# MCU.net
KiCad netlist of a schematic drawn in Altium Designer
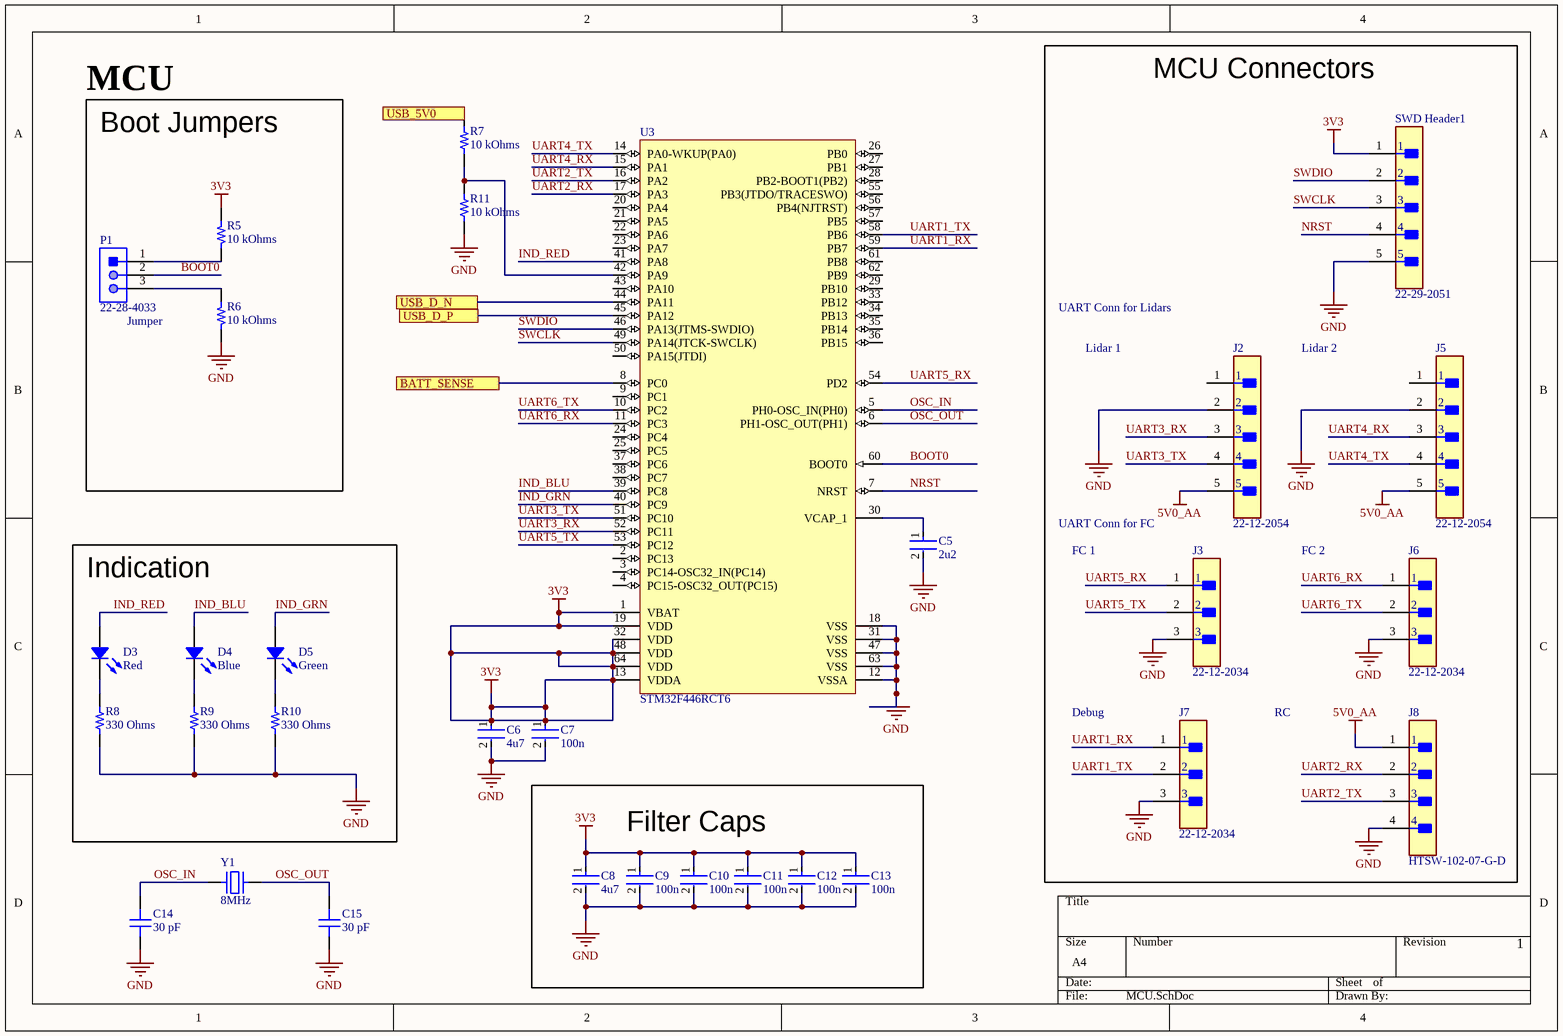
[diagram p0: MCU.SchDoc]

(export (version "E")
  (design (tool "Eeschema 10.0.6"))
  (components
    (comp (ref "C5")
      (value "2u2")
      (footprint "FP-CL10-IPC_C")
      (description "Cap Ceramic 4.7uF 10V X5R ±10% Pad SMD 0603 +85°C T/R")
      (fields (field (name "TOLERANCE") "10%"))
      (libsource (lib "Altium Content Vault") (part "b4654b650e69147ec39a6b967a45e02"))
    )
    (comp (ref "C6")
      (value "4u7")
      (footprint "FP-CL10-IPC_C")
      (description "Cap Ceramic 4.7uF 10V X5R ±10% Pad SMD 0603 +85°C T/R")
      (fields (field (name "TOLERANCE") "10%"))
      (libsource (lib "Altium Content Vault") (part "b4654b650e69147ec39a6b967a45e02"))
    )
    (comp (ref "C7")
      (value "100n")
      (footprint "FP-CL779-IPC_C")
      (description "Cap Ceramic 100nF 50V X7R ±10% SMD 0402 +125°C Paper T/R")
      (libsource (lib "Altium Content Vault") (part "b4654b650e69147ec39a6b967a45e02"))
    )
    (comp (ref "C8")
      (value "4u7")
      (footprint "FP-CL10-IPC_C")
      (description "Cap Ceramic 4.7uF 10V X5R ±10% Pad SMD 0603 +85°C T/R")
      (fields (field (name "TOLERANCE") "10%"))
      (libsource (lib "Altium Content Vault") (part "b4654b650e69147ec39a6b967a45e02"))
    )
    (comp (ref "C9")
      (value "100n")
      (footprint "FP-CL779-IPC_C")
      (description "Cap Ceramic 100nF 50V X7R ±10% SMD 0402 +125°C Paper T/R")
      (libsource (lib "Altium Content Vault") (part "b4654b650e69147ec39a6b967a45e02"))
    )
    (comp (ref "C10")
      (value "100n")
      (footprint "FP-CL779-IPC_C")
      (description "Cap Ceramic 100nF 50V X7R ±10% SMD 0402 +125°C Paper T/R")
      (libsource (lib "Altium Content Vault") (part "b4654b650e69147ec39a6b967a45e02"))
    )
    (comp (ref "C11")
      (value "100n")
      (footprint "FP-CL779-IPC_C")
      (description "Cap Ceramic 100nF 50V X7R ±10% SMD 0402 +125°C Paper T/R")
      (libsource (lib "Altium Content Vault") (part "b4654b650e69147ec39a6b967a45e02"))
    )
    (comp (ref "C12")
      (value "100n")
      (footprint "FP-CL779-IPC_C")
      (description "Cap Ceramic 100nF 50V X7R ±10% SMD 0402 +125°C Paper T/R")
      (libsource (lib "Altium Content Vault") (part "b4654b650e69147ec39a6b967a45e02"))
    )
    (comp (ref "C13")
      (value "100n")
      (footprint "FP-CL779-IPC_C")
      (description "Cap Ceramic 100nF 50V X7R ±10% SMD 0402 +125°C Paper T/R")
      (libsource (lib "Altium Content Vault") (part "b4654b650e69147ec39a6b967a45e02"))
    )
    (comp (ref "C14")
      (value "30 pF")
      (footprint "CAP 0603_1608")
      (description "CAP CER 30PF 50V C0G/NP0 0603")
      (fields
        (field (name "PART NUMBER") "0603N300J500CT")
        (field (name "MANUFACTURER") "Walsin Technology Corporation")
      )
      (libsource (lib "Celestial Altium Library - altium_library") (part "Capacitor"))
    )
    (comp (ref "C15")
      (value "30 pF")
      (footprint "CAP 0603_1608")
      (description "CAP CER 30PF 50V C0G/NP0 0603")
      (fields
        (field (name "PART NUMBER") "0603N300J500CT")
        (field (name "MANUFACTURER") "Walsin Technology Corporation")
      )
      (libsource (lib "Celestial Altium Library - altium_library") (part "Capacitor"))
    )
    (comp (ref "D3")
      (value "Red")
      (footprint "LED 0603_1608 RED")
      (description "LED RED CLEAR 2SMD")
      (fields
        (field (name "PART NUMBER") "19-213SDRC/S259/TR8")
        (field (name "MANUFACTURER") "Everlight Electronics Co Ltd")
      )
      (libsource (lib "Celestial Altium Library - altium_library") (part "LED"))
    )
    (comp (ref "D4")
      (value "Blue")
      (footprint "LED 0603_1608 BLUE")
      (description "LED BLUE CLEAR 2SMD")
      (fields
        (field (name "PART NUMBER") "19-213SUBC/S400-A5/S208-2/TR8")
        (field (name "MANUFACTURER") "Everlight Electronics Co Ltd")
      )
      (libsource (lib "Celestial Altium Library - altium_library") (part "LED"))
    )
    (comp (ref "D5")
      (value "Green")
      (footprint "LED 0603_1608 GREEN")
      (description "LED GREEN DIFFUSED 0603 SMD")
      (fields (field (name "PART NUMBER") "150060GS55040") (field (name "MANUFACTURER") "Würth Elektronik"))
      (libsource (lib "Celestial Altium Library - altium_library") (part "LED"))
    )
    (comp (ref "J2")
      (value "22-12-2054")
      (footprint "FP-22-12-2054-MFG")
      (libsource (lib "Altium Content Vault") (part "bf93c07fd2649a848d0ec8585582aab"))
    )
    (comp (ref "J3")
      (value "22-12-2034")
      (footprint "FP-22-12-2034-MFG")
      (description "CONN HEADER R/A 3POS 2.54MM")
      (libsource (lib "Altium Content Vault") (part "0d3f023dd272f625e17a2be33dea85f"))
    )
    (comp (ref "J5")
      (value "22-12-2054")
      (footprint "FP-22-12-2054-MFG")
      (libsource (lib "Altium Content Vault") (part "bf93c07fd2649a848d0ec8585582aab"))
    )
    (comp (ref "J6")
      (value "22-12-2034")
      (footprint "FP-22-12-2034-MFG")
      (description "CONN HEADER R/A 3POS 2.54MM")
      (libsource (lib "Altium Content Vault") (part "0d3f023dd272f625e17a2be33dea85f"))
    )
    (comp (ref "J7")
      (value "22-12-2034")
      (footprint "FP-22-12-2034-MFG")
      (description "CONN HEADER R/A 3POS 2.54MM")
      (libsource (lib "Altium Content Vault") (part "0d3f023dd272f625e17a2be33dea85f"))
    )
    (comp (ref "J8")
      (value "HTSW-102-07-G-D")
      (footprint "FP-HTSW-102-07-G-D-MFG")
      (description "Connector Header Through Hole 4 position 0.100\" (2.54mm)")
      (fields (field (name "MANUFACTURER") "Samtec"))
      (libsource (lib "Altium Content Vault") (part "299a8cea1bdcbc3624fe62c390fa72c"))
    )
    (comp (ref "P1")
      (value "22-28-4033")
      (footprint "MOLX-22-28-4033_V")
      (description "Male Header, Pitch 2.54 mm, 1 x 3 Position, Height 8.38 mm, Tail Length 3.18 mm, RoHS, Bulk")
      (fields (field (name "MANUFACTURER") "Molex"))
      (libsource (lib "Altium Content Vault") (part "CN-1P-M-R3"))
    )
    (comp (ref "R5")
      (value "10 kOhms")
      (footprint "RES 0603_1608")
      (description "P2TC0603 2PPM/C 10K 0,01% N TA")
      (fields
        (field (name "PART NUMBER") "P2TC0603D1002LNTA")
        (field (name "MANUFACTURER") "Vishay Sfernice")
      )
      (libsource (lib "Celestial Altium Library - altium_library") (part "Resistor"))
    )
    (comp (ref "R6")
      (value "10 kOhms")
      (footprint "RES 0603_1608")
      (description "P2TC0603 2PPM/C 10K 0,01% N TA")
      (fields
        (field (name "PART NUMBER") "P2TC0603D1002LNTA")
        (field (name "MANUFACTURER") "Vishay Sfernice")
      )
      (libsource (lib "Celestial Altium Library - altium_library") (part "Resistor"))
    )
    (comp (ref "R7")
      (value "10 kOhms")
      (footprint "RES 0603_1608")
      (description "1/16 WATTS PRECISION CHIP 10 KIL")
      (fields (field (name "PART NUMBER") "APC0603B10K0N") (field (name "MANUFACTURER") "Ohmite"))
      (libsource (lib "Celestial Altium Library - altium_library") (part "Resistor"))
    )
    (comp (ref "R8")
      (value "330 Ohms")
      (footprint "RES 0603_1608")
      (description "RCC0603 100 330R 1% ET1 E3")
      (fields (field (name "PART NUMBER") "RCC0603330RFKEA") (field (name "MANUFACTURER") "Vishay Dale"))
      (libsource (lib "Celestial Altium Library - altium_library") (part "Resistor"))
    )
    (comp (ref "R9")
      (value "330 Ohms")
      (footprint "RES 0603_1608")
      (description "RCC0603 100 330R 1% ET1 E3")
      (fields (field (name "PART NUMBER") "RCC0603330RFKEA") (field (name "MANUFACTURER") "Vishay Dale"))
      (libsource (lib "Celestial Altium Library - altium_library") (part "Resistor"))
    )
    (comp (ref "R10")
      (value "330 Ohms")
      (footprint "RES 0603_1608")
      (description "RCC0603 100 330R 1% ET1 E3")
      (fields (field (name "PART NUMBER") "RCC0603330RFKEA") (field (name "MANUFACTURER") "Vishay Dale"))
      (libsource (lib "Celestial Altium Library - altium_library") (part "Resistor"))
    )
    (comp (ref "R11")
      (value "10 kOhms")
      (footprint "RES 0603_1608")
      (description "1/16 WATTS PRECISION CHIP 10 KIL")
      (fields (field (name "PART NUMBER") "APC0603B10K0N") (field (name "MANUFACTURER") "Ohmite"))
      (libsource (lib "Celestial Altium Library - altium_library") (part "Resistor"))
    )
    (comp (ref "SWD Header1")
      (value "22-29-2051")
      (footprint "FP-22-29-2051-MFG")
      (description "2.54MM KK HDR VT FRICLK VRA .5AU")
      (libsource (lib "Altium Content Vault") (part "bf93c07fd2649a848d0ec8585582aab"))
    )
    (comp (ref "U3")
      (value "STM32F446RCT6")
      (footprint "STM-LQFP64_L")
      (libsource (lib "Altium Content Vault") (part "MC-ARM-STM32F446-LQFP64"))
    )
    (comp (ref "Y1")
      (value "8MHz")
      (footprint "TXC 9C")
      (description "CRYSTAL 8.0000MHZ 20PF SMD")
      (fields (field (name "PART NUMBER") "9C-8.000MBBK-T") (field (name "MANUFACTURER") "TXC CORPORATION"))
      (libsource (lib "Celestial Altium Library - altium_library") (part "TXC Crystal 9C"))
    )
  )
  (nets
    (net (code "1") (name "/BATT_SENSE") (class "Default")
      (node (ref "U3") (pin "8") (pinfunction "PC0_8") (pintype "bidirectional"))
    )
    (net (code "2") (name "/BOOT0") (class "Default")
      (node (ref "P1") (pin "2") (pinfunction "2_2") (pintype "passive"))
      (node (ref "U3") (pin "60") (pinfunction "BOOT0_60") (pintype "input"))
    )
    (net (code "3") (name "/IND_BLU") (class "Default")
      (node (ref "D4") (pin "1") (pinfunction "1_1") (pintype "passive"))
      (node (ref "U3") (pin "39") (pinfunction "PC8_39") (pintype "bidirectional"))
    )
    (net (code "4") (name "/IND_GRN") (class "Default")
      (node (ref "D5") (pin "1") (pinfunction "1_1") (pintype "passive"))
      (node (ref "U3") (pin "40") (pinfunction "PC9_40") (pintype "bidirectional"))
    )
    (net (code "5") (name "/IND_RED") (class "Default")
      (node (ref "D3") (pin "1") (pinfunction "1_1") (pintype "passive"))
      (node (ref "U3") (pin "41") (pinfunction "PA8_41") (pintype "bidirectional"))
    )
    (net (code "6") (name "/NRST") (class "Default")
      (node (ref "SWD Header1") (pin "4") (pinfunction "4_4") (pintype "passive"))
      (node (ref "U3") (pin "7") (pinfunction "NRST_7") (pintype "bidirectional"))
    )
    (net (code "7") (name "/OSC_IN") (class "Default")
      (node (ref "C14") (pin "2") (pinfunction "2_2") (pintype "passive"))
      (node (ref "U3") (pin "5") (pinfunction "PH0-OSC_IN(PH0)_5") (pintype "bidirectional"))
      (node (ref "Y1") (pin "1") (pinfunction "1_1") (pintype "passive"))
    )
    (net (code "8") (name "/OSC_OUT") (class "Default")
      (node (ref "C15") (pin "2") (pinfunction "2_2") (pintype "passive"))
      (node (ref "U3") (pin "6") (pinfunction "PH1-OSC_OUT(PH1)_6") (pintype "bidirectional"))
      (node (ref "Y1") (pin "2") (pinfunction "2_2") (pintype "passive"))
    )
    (net (code "9") (name "/SWCLK") (class "Default")
      (node (ref "SWD Header1") (pin "3") (pinfunction "3_3") (pintype "passive"))
      (node (ref "U3") (pin "49") (pinfunction "PA14(JTCK-SWCLK)_49") (pintype "bidirectional"))
    )
    (net (code "10") (name "/SWDIO") (class "Default")
      (node (ref "SWD Header1") (pin "2") (pinfunction "2_2") (pintype "passive"))
      (node (ref "U3") (pin "46") (pinfunction "PA13(JTMS-SWDIO)_46") (pintype "bidirectional"))
    )
    (net (code "11") (name "/UART1_RX") (class "Default")
      (node (ref "J7") (pin "1") (pinfunction "1_1") (pintype "passive"))
      (node (ref "U3") (pin "59") (pinfunction "PB7_59") (pintype "bidirectional"))
    )
    (net (code "12") (name "/UART1_TX") (class "Default")
      (node (ref "J7") (pin "2") (pinfunction "2_2") (pintype "passive"))
      (node (ref "U3") (pin "58") (pinfunction "PB6_58") (pintype "bidirectional"))
    )
    (net (code "13") (name "/UART2_RX") (class "Default")
      (node (ref "J8") (pin "2") (pinfunction "2_2") (pintype "passive"))
      (node (ref "U3") (pin "17") (pinfunction "PA3_17") (pintype "bidirectional"))
    )
    (net (code "14") (name "/UART2_TX") (class "Default")
      (node (ref "J8") (pin "3") (pinfunction "3_3") (pintype "passive"))
      (node (ref "U3") (pin "16") (pinfunction "PA2_16") (pintype "bidirectional"))
    )
    (net (code "15") (name "/UART3_RX") (class "Default")
      (node (ref "J2") (pin "3") (pinfunction "3_3") (pintype "passive"))
      (node (ref "U3") (pin "52") (pinfunction "PC11_52") (pintype "bidirectional"))
    )
    (net (code "16") (name "/UART3_TX") (class "Default")
      (node (ref "J2") (pin "4") (pinfunction "4_4") (pintype "passive"))
      (node (ref "U3") (pin "51") (pinfunction "PC10_51") (pintype "bidirectional"))
    )
    (net (code "17") (name "/UART4_RX") (class "Default")
      (node (ref "J5") (pin "3") (pinfunction "3_3") (pintype "passive"))
      (node (ref "U3") (pin "15") (pinfunction "PA1_15") (pintype "bidirectional"))
    )
    (net (code "18") (name "/UART4_TX") (class "Default")
      (node (ref "J5") (pin "4") (pinfunction "4_4") (pintype "passive"))
      (node (ref "U3") (pin "14") (pinfunction "PA0-WKUP(PA0)_14") (pintype "bidirectional"))
    )
    (net (code "19") (name "/UART5_RX") (class "Default")
      (node (ref "J3") (pin "1") (pinfunction "1_1") (pintype "passive"))
      (node (ref "U3") (pin "54") (pinfunction "PD2_54") (pintype "bidirectional"))
    )
    (net (code "20") (name "/UART5_TX") (class "Default")
      (node (ref "J3") (pin "2") (pinfunction "2_2") (pintype "passive"))
      (node (ref "U3") (pin "53") (pinfunction "PC12_53") (pintype "bidirectional"))
    )
    (net (code "21") (name "/UART6_RX") (class "Default")
      (node (ref "J6") (pin "1") (pinfunction "1_1") (pintype "passive"))
      (node (ref "U3") (pin "11") (pinfunction "PC3_11") (pintype "bidirectional"))
    )
    (net (code "22") (name "/UART6_TX") (class "Default")
      (node (ref "J6") (pin "2") (pinfunction "2_2") (pintype "passive"))
      (node (ref "U3") (pin "10") (pinfunction "PC2_10") (pintype "bidirectional"))
    )
    (net (code "23") (name "/USB_5V0") (class "Default")
      (node (ref "R7") (pin "2") (pinfunction "2_2") (pintype "passive"))
    )
    (net (code "24") (name "/USB_D_N") (class "Default")
      (node (ref "U3") (pin "44") (pinfunction "PA11_44") (pintype "bidirectional"))
    )
    (net (code "25") (name "/USB_D_P") (class "Default")
      (node (ref "U3") (pin "45") (pinfunction "PA12_45") (pintype "bidirectional"))
    )
    (net (code "26") (name "3V3") (class "Default")
      (node (ref "C10") (pin "1") (pinfunction "1_1") (pintype "passive"))
      (node (ref "C11") (pin "1") (pinfunction "1_1") (pintype "passive"))
      (node (ref "C12") (pin "1") (pinfunction "1_1") (pintype "passive"))
      (node (ref "C13") (pin "1") (pinfunction "1_1") (pintype "passive"))
      (node (ref "C6") (pin "1") (pinfunction "1_1") (pintype "passive"))
      (node (ref "C7") (pin "1") (pinfunction "1_1") (pintype "passive"))
      (node (ref "C8") (pin "1") (pinfunction "1_1") (pintype "passive"))
      (node (ref "C9") (pin "1") (pinfunction "1_1") (pintype "passive"))
      (node (ref "R5") (pin "1") (pinfunction "1_1") (pintype "passive"))
      (node (ref "SWD Header1") (pin "1") (pinfunction "1_1") (pintype "passive"))
      (node (ref "U3") (pin "1") (pinfunction "VBAT_1") (pintype "power_in"))
      (node (ref "U3") (pin "13") (pinfunction "VDDA_13") (pintype "power_in"))
      (node (ref "U3") (pin "19") (pinfunction "VDD_19") (pintype "power_in"))
      (node (ref "U3") (pin "32") (pinfunction "VDD_32") (pintype "power_in"))
      (node (ref "U3") (pin "48") (pinfunction "VDD_48") (pintype "power_in"))
      (node (ref "U3") (pin "64") (pinfunction "VDD_64") (pintype "power_in"))
    )
    (net (code "27") (name "5V0_AA") (class "Default")
      (node (ref "J2") (pin "5") (pinfunction "5_5") (pintype "passive"))
      (node (ref "J5") (pin "5") (pinfunction "5_5") (pintype "passive"))
      (node (ref "J8") (pin "1") (pinfunction "1_1") (pintype "passive"))
    )
    (net (code "28") (name "GND") (class "Default")
      (node (ref "C10") (pin "2") (pinfunction "2_2") (pintype "passive"))
      (node (ref "C11") (pin "2") (pinfunction "2_2") (pintype "passive"))
      (node (ref "C12") (pin "2") (pinfunction "2_2") (pintype "passive"))
      (node (ref "C13") (pin "2") (pinfunction "2_2") (pintype "passive"))
      (node (ref "C14") (pin "1") (pinfunction "1_1") (pintype "passive"))
      (node (ref "C15") (pin "1") (pinfunction "1_1") (pintype "passive"))
      (node (ref "C5") (pin "2") (pinfunction "2_2") (pintype "passive"))
      (node (ref "C6") (pin "2") (pinfunction "2_2") (pintype "passive"))
      (node (ref "C7") (pin "2") (pinfunction "2_2") (pintype "passive"))
      (node (ref "C8") (pin "2") (pinfunction "2_2") (pintype "passive"))
      (node (ref "C9") (pin "2") (pinfunction "2_2") (pintype "passive"))
      (node (ref "J2") (pin "2") (pinfunction "2_2") (pintype "passive"))
      (node (ref "J3") (pin "3") (pinfunction "3_3") (pintype "passive"))
      (node (ref "J5") (pin "2") (pinfunction "2_2") (pintype "passive"))
      (node (ref "J6") (pin "3") (pinfunction "3_3") (pintype "passive"))
      (node (ref "J7") (pin "3") (pinfunction "3_3") (pintype "passive"))
      (node (ref "J8") (pin "4") (pinfunction "4_4") (pintype "passive"))
      (node (ref "R10") (pin "1") (pinfunction "1_1") (pintype "passive"))
      (node (ref "R11") (pin "1") (pinfunction "1_1") (pintype "passive"))
      (node (ref "R6") (pin "1") (pinfunction "1_1") (pintype "passive"))
      (node (ref "R8") (pin "1") (pinfunction "1_1") (pintype "passive"))
      (node (ref "R9") (pin "1") (pinfunction "1_1") (pintype "passive"))
      (node (ref "SWD Header1") (pin "5") (pinfunction "5_5") (pintype "passive"))
      (node (ref "U3") (pin "12") (pinfunction "VSSA_12") (pintype "power_in"))
      (node (ref "U3") (pin "18") (pinfunction "VSS_18") (pintype "power_in"))
      (node (ref "U3") (pin "31") (pinfunction "VSS_31") (pintype "power_in"))
      (node (ref "U3") (pin "47") (pinfunction "VSS_47") (pintype "power_in"))
      (node (ref "U3") (pin "63") (pinfunction "VSS_63") (pintype "power_in"))
    )
    (net (code "29") (name "Net-(D3-Pad2)") (class "Default")
      (node (ref "D3") (pin "2") (pinfunction "2_2") (pintype "passive"))
      (node (ref "R8") (pin "2") (pinfunction "2_2") (pintype "passive"))
    )
    (net (code "30") (name "Net-(D4-Pad2)") (class "Default")
      (node (ref "D4") (pin "2") (pinfunction "2_2") (pintype "passive"))
      (node (ref "R9") (pin "2") (pinfunction "2_2") (pintype "passive"))
    )
    (net (code "31") (name "Net-(D5-Pad2)") (class "Default")
      (node (ref "D5") (pin "2") (pinfunction "2_2") (pintype "passive"))
      (node (ref "R10") (pin "2") (pinfunction "2_2") (pintype "passive"))
    )
    (net (code "32") (name "Net-(P1-Pad1)") (class "Default")
      (node (ref "P1") (pin "1") (pinfunction "1_1") (pintype "passive"))
      (node (ref "R5") (pin "2") (pinfunction "2_2") (pintype "passive"))
    )
    (net (code "33") (name "Net-(P1-Pad3)") (class "Default")
      (node (ref "P1") (pin "3") (pinfunction "3_3") (pintype "passive"))
      (node (ref "R6") (pin "2") (pinfunction "2_2") (pintype "passive"))
    )
    (net (code "34") (name "Net-(U3-PA9)") (class "Default")
      (node (ref "R11") (pin "2") (pinfunction "2_2") (pintype "passive"))
      (node (ref "R7") (pin "1") (pinfunction "1_1") (pintype "passive"))
      (node (ref "U3") (pin "42") (pinfunction "PA9_42") (pintype "bidirectional"))
    )
    (net (code "35") (name "Net-(U3-VCAP_1)") (class "Default")
      (node (ref "C5") (pin "1") (pinfunction "1_1") (pintype "passive"))
      (node (ref "U3") (pin "30") (pinfunction "VCAP_1_30") (pintype "passive"))
    )
    (net (code "36") (name "unconnected-(J2-Pad1)") (class "Default")
      (node (ref "J2") (pin "1") (pinfunction "1_1") (pintype "passive"))
    )
    (net (code "37") (name "unconnected-(J5-Pad1)") (class "Default")
      (node (ref "J5") (pin "1") (pinfunction "1_1") (pintype "passive"))
    )
    (net (code "38") (name "unconnected-(U3-PA4-Pad20)") (class "Default")
      (node (ref "U3") (pin "20") (pinfunction "PA4_20") (pintype "bidirectional"))
    )
    (net (code "39") (name "unconnected-(U3-PA5-Pad21)") (class "Default")
      (node (ref "U3") (pin "21") (pinfunction "PA5_21") (pintype "bidirectional"))
    )
    (net (code "40") (name "unconnected-(U3-PA6-Pad22)") (class "Default")
      (node (ref "U3") (pin "22") (pinfunction "PA6_22") (pintype "bidirectional"))
    )
    (net (code "41") (name "unconnected-(U3-PA7-Pad23)") (class "Default")
      (node (ref "U3") (pin "23") (pinfunction "PA7_23") (pintype "bidirectional"))
    )
    (net (code "42") (name "unconnected-(U3-PA10-Pad43)") (class "Default")
      (node (ref "U3") (pin "43") (pinfunction "PA10_43") (pintype "bidirectional"))
    )
    (net (code "43") (name "unconnected-(U3-PA15(JTDI)-Pad50)") (class "Default")
      (node (ref "U3") (pin "50") (pinfunction "PA15(JTDI)_50") (pintype "bidirectional"))
    )
    (net (code "44") (name "unconnected-(U3-PB0-Pad26)") (class "Default")
      (node (ref "U3") (pin "26") (pinfunction "PB0_26") (pintype "bidirectional"))
    )
    (net (code "45") (name "unconnected-(U3-PB1-Pad27)") (class "Default")
      (node (ref "U3") (pin "27") (pinfunction "PB1_27") (pintype "bidirectional"))
    )
    (net (code "46") (name "unconnected-(U3-PB2-BOOT1(PB2)-Pad28)") (class "Default")
      (node (ref "U3") (pin "28") (pinfunction "PB2-BOOT1(PB2)_28") (pintype "bidirectional"))
    )
    (net (code "47") (name "unconnected-(U3-PB3(JTDO{slash}TRACESWO)-Pad55)") (class "Default")
      (node (ref "U3") (pin "55") (pinfunction "PB3(JTDO/TRACESWO)_55") (pintype "bidirectional"))
    )
    (net (code "48") (name "unconnected-(U3-PB4(NJTRST)-Pad56)") (class "Default")
      (node (ref "U3") (pin "56") (pinfunction "PB4(NJTRST)_56") (pintype "bidirectional"))
    )
    (net (code "49") (name "unconnected-(U3-PB5-Pad57)") (class "Default")
      (node (ref "U3") (pin "57") (pinfunction "PB5_57") (pintype "bidirectional"))
    )
    (net (code "50") (name "unconnected-(U3-PB8-Pad61)") (class "Default")
      (node (ref "U3") (pin "61") (pinfunction "PB8_61") (pintype "bidirectional"))
    )
    (net (code "51") (name "unconnected-(U3-PB9-Pad62)") (class "Default")
      (node (ref "U3") (pin "62") (pinfunction "PB9_62") (pintype "bidirectional"))
    )
    (net (code "52") (name "unconnected-(U3-PB10-Pad29)") (class "Default")
      (node (ref "U3") (pin "29") (pinfunction "PB10_29") (pintype "bidirectional"))
    )
    (net (code "53") (name "unconnected-(U3-PB12-Pad33)") (class "Default")
      (node (ref "U3") (pin "33") (pinfunction "PB12_33") (pintype "bidirectional"))
    )
    (net (code "54") (name "unconnected-(U3-PB13-Pad34)") (class "Default")
      (node (ref "U3") (pin "34") (pinfunction "PB13_34") (pintype "bidirectional"))
    )
    (net (code "55") (name "unconnected-(U3-PB14-Pad35)") (class "Default")
      (node (ref "U3") (pin "35") (pinfunction "PB14_35") (pintype "bidirectional"))
    )
    (net (code "56") (name "unconnected-(U3-PB15-Pad36)") (class "Default")
      (node (ref "U3") (pin "36") (pinfunction "PB15_36") (pintype "bidirectional"))
    )
    (net (code "57") (name "unconnected-(U3-PC1-Pad9)") (class "Default")
      (node (ref "U3") (pin "9") (pinfunction "PC1_9") (pintype "bidirectional"))
    )
    (net (code "58") (name "unconnected-(U3-PC4-Pad24)") (class "Default")
      (node (ref "U3") (pin "24") (pinfunction "PC4_24") (pintype "bidirectional"))
    )
    (net (code "59") (name "unconnected-(U3-PC5-Pad25)") (class "Default")
      (node (ref "U3") (pin "25") (pinfunction "PC5_25") (pintype "bidirectional"))
    )
    (net (code "60") (name "unconnected-(U3-PC6-Pad37)") (class "Default")
      (node (ref "U3") (pin "37") (pinfunction "PC6_37") (pintype "bidirectional"))
    )
    (net (code "61") (name "unconnected-(U3-PC7-Pad38)") (class "Default")
      (node (ref "U3") (pin "38") (pinfunction "PC7_38") (pintype "bidirectional"))
    )
    (net (code "62") (name "unconnected-(U3-PC13-Pad2)") (class "Default")
      (node (ref "U3") (pin "2") (pinfunction "PC13_2") (pintype "bidirectional"))
    )
    (net (code "63") (name "unconnected-(U3-PC14-OSC32_IN(PC14)-Pad3)") (class "Default")
      (node (ref "U3") (pin "3") (pinfunction "PC14-OSC32_IN(PC14)_3") (pintype "bidirectional"))
    )
    (net (code "64") (name "unconnected-(U3-PC15-OSC32_OUT(PC15)-Pad4)") (class "Default")
      (node (ref "U3") (pin "4") (pinfunction "PC15-OSC32_OUT(PC15)_4") (pintype "bidirectional"))
    )
  )
)
